# SCH_Slave.net
KiCad netlist of a schematic drawn in Altium Designer
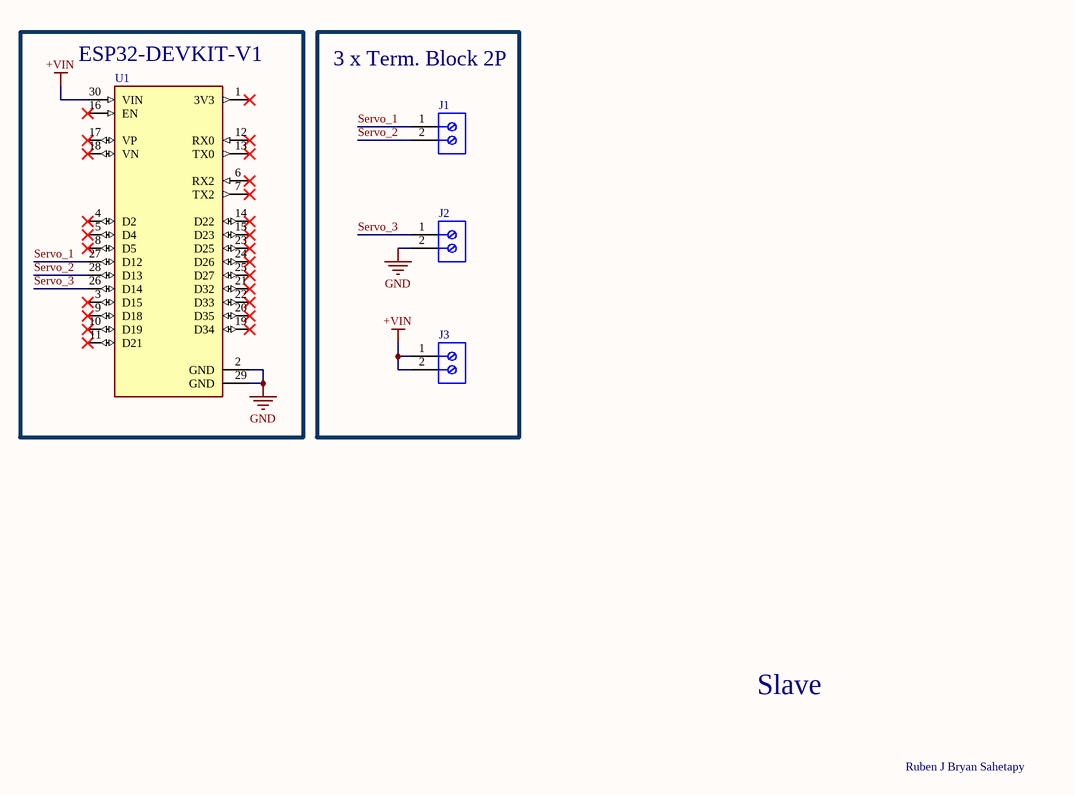
[diagram p0: SCH_Slave.SchDoc]

(export (version "E")
  (design (tool "Eeschema 10.0.6"))
  (components
    (comp (ref "J1")
      (value "Term. Block 2P")
      (footprint "691253410002")
      (description "Terminal Block, 7.62MM Pitch, Horizontal, Rising Cage Clamp, 12-30 AWG, 2 Pin")
      (libsource (lib "Altium Content Vault") (part "TBL - 1R - 02P - Screw"))
    )
    (comp (ref "J2")
      (value "Term. Block 2P")
      (footprint "691253410002")
      (description "Terminal Block, 7.62MM Pitch, Horizontal, Rising Cage Clamp, 12-30 AWG, 2 Pin")
      (libsource (lib "Altium Content Vault") (part "TBL - 1R - 02P - Screw"))
    )
    (comp (ref "J3")
      (value "3 x Term. Block 2P")
      (footprint "691253410002")
      (description "Terminal Block, 7.62MM Pitch, Horizontal, Rising Cage Clamp, 12-30 AWG, 2 Pin")
      (libsource (lib "Altium Content Vault") (part "TBL - 1R - 02P - Screw"))
    )
    (comp (ref "U1")
      (value "ESP32-DEVKIT-V1")
      (footprint "MODULE_ESP32_DEVKIT_V1")
      (description "ESP32-DEVKIT-V1 30 Pins")
      (fields (field (name "MF") "Do it"))
      (libsource (lib "MarbleLib") (part "ESP32-DEVKIT-V1"))
    )
  )
  (nets
    (net (code "1") (name "+VIN") (class "Default")
      (node (ref "J3") (pin "1") (pinfunction "1_1") (pintype "passive"))
      (node (ref "J3") (pin "2") (pinfunction "2_2") (pintype "passive"))
      (node (ref "U1") (pin "30") (pinfunction "VIN_30") (pintype "input"))
    )
    (net (code "2") (name "/Servo_1") (class "Default")
      (node (ref "J1") (pin "1") (pinfunction "1_1") (pintype "passive"))
      (node (ref "U1") (pin "27") (pinfunction "D12_27") (pintype "bidirectional"))
    )
    (net (code "3") (name "/Servo_2") (class "Default")
      (node (ref "J1") (pin "2") (pinfunction "2_2") (pintype "passive"))
      (node (ref "U1") (pin "28") (pinfunction "D13_28") (pintype "bidirectional"))
    )
    (net (code "4") (name "/Servo_3") (class "Default")
      (node (ref "J2") (pin "1") (pinfunction "1_1") (pintype "passive"))
      (node (ref "U1") (pin "26") (pinfunction "D14_26") (pintype "bidirectional"))
    )
    (net (code "5") (name "GND") (class "Default")
      (node (ref "J2") (pin "2") (pinfunction "2_2") (pintype "passive"))
      (node (ref "U1") (pin "2") (pinfunction "GND_2") (pintype "power_in"))
      (node (ref "U1") (pin "29") (pinfunction "GND_29") (pintype "power_in"))
    )
    (net (code "6") (name "unconnected-(U1-3V3-Pad1)") (class "Default")
      (node (ref "U1") (pin "1") (pinfunction "3V3_1") (pintype "output+no_connect"))
    )
    (net (code "7") (name "unconnected-(U1-D2-Pad4)") (class "Default")
      (node (ref "U1") (pin "4") (pinfunction "D2_4") (pintype "bidirectional+no_connect"))
    )
    (net (code "8") (name "unconnected-(U1-D4-Pad5)") (class "Default")
      (node (ref "U1") (pin "5") (pinfunction "D4_5") (pintype "bidirectional+no_connect"))
    )
    (net (code "9") (name "unconnected-(U1-D5-Pad8)") (class "Default")
      (node (ref "U1") (pin "8") (pinfunction "D5_8") (pintype "bidirectional+no_connect"))
    )
    (net (code "10") (name "unconnected-(U1-D15-Pad3)") (class "Default")
      (node (ref "U1") (pin "3") (pinfunction "D15_3") (pintype "bidirectional+no_connect"))
    )
    (net (code "11") (name "unconnected-(U1-D18-Pad9)") (class "Default")
      (node (ref "U1") (pin "9") (pinfunction "D18_9") (pintype "bidirectional+no_connect"))
    )
    (net (code "12") (name "unconnected-(U1-D19-Pad10)") (class "Default")
      (node (ref "U1") (pin "10") (pinfunction "D19_10") (pintype "bidirectional+no_connect"))
    )
    (net (code "13") (name "unconnected-(U1-D21-Pad11)") (class "Default")
      (node (ref "U1") (pin "11") (pinfunction "D21_11") (pintype "bidirectional+no_connect"))
    )
    (net (code "14") (name "unconnected-(U1-D22-Pad14)") (class "Default")
      (node (ref "U1") (pin "14") (pinfunction "D22_14") (pintype "bidirectional+no_connect"))
    )
    (net (code "15") (name "unconnected-(U1-D23-Pad15)") (class "Default")
      (node (ref "U1") (pin "15") (pinfunction "D23_15") (pintype "bidirectional+no_connect"))
    )
    (net (code "16") (name "unconnected-(U1-D25-Pad23)") (class "Default")
      (node (ref "U1") (pin "23") (pinfunction "D25_23") (pintype "bidirectional+no_connect"))
    )
    (net (code "17") (name "unconnected-(U1-D26-Pad24)") (class "Default")
      (node (ref "U1") (pin "24") (pinfunction "D26_24") (pintype "bidirectional+no_connect"))
    )
    (net (code "18") (name "unconnected-(U1-D27-Pad25)") (class "Default")
      (node (ref "U1") (pin "25") (pinfunction "D27_25") (pintype "bidirectional+no_connect"))
    )
    (net (code "19") (name "unconnected-(U1-D32-Pad21)") (class "Default")
      (node (ref "U1") (pin "21") (pinfunction "D32_21") (pintype "bidirectional+no_connect"))
    )
    (net (code "20") (name "unconnected-(U1-D33-Pad22)") (class "Default")
      (node (ref "U1") (pin "22") (pinfunction "D33_22") (pintype "bidirectional+no_connect"))
    )
    (net (code "21") (name "unconnected-(U1-D34-Pad19)") (class "Default")
      (node (ref "U1") (pin "19") (pinfunction "D34_19") (pintype "bidirectional+no_connect"))
    )
    (net (code "22") (name "unconnected-(U1-D35-Pad20)") (class "Default")
      (node (ref "U1") (pin "20") (pinfunction "D35_20") (pintype "bidirectional+no_connect"))
    )
    (net (code "23") (name "unconnected-(U1-EN-Pad16)") (class "Default")
      (node (ref "U1") (pin "16") (pinfunction "EN_16") (pintype "input+no_connect"))
    )
    (net (code "24") (name "unconnected-(U1-RX0-Pad12)") (class "Default")
      (node (ref "U1") (pin "12") (pinfunction "RX0_12") (pintype "input+no_connect"))
    )
    (net (code "25") (name "unconnected-(U1-RX2-Pad6)") (class "Default")
      (node (ref "U1") (pin "6") (pinfunction "RX2_6") (pintype "input+no_connect"))
    )
    (net (code "26") (name "unconnected-(U1-TX0-Pad13)") (class "Default")
      (node (ref "U1") (pin "13") (pinfunction "TX0_13") (pintype "output+no_connect"))
    )
    (net (code "27") (name "unconnected-(U1-TX2-Pad7)") (class "Default")
      (node (ref "U1") (pin "7") (pinfunction "TX2_7") (pintype "output+no_connect"))
    )
    (net (code "28") (name "unconnected-(U1-VN-Pad18)") (class "Default")
      (node (ref "U1") (pin "18") (pinfunction "VN_18") (pintype "bidirectional+no_connect"))
    )
    (net (code "29") (name "unconnected-(U1-VP-Pad17)") (class "Default")
      (node (ref "U1") (pin "17") (pinfunction "VP_17") (pintype "bidirectional+no_connect"))
    )
  )
)
